# ITKS_685623_177_E3.net
KiCad netlist of a schematic drawn in Altium Designer
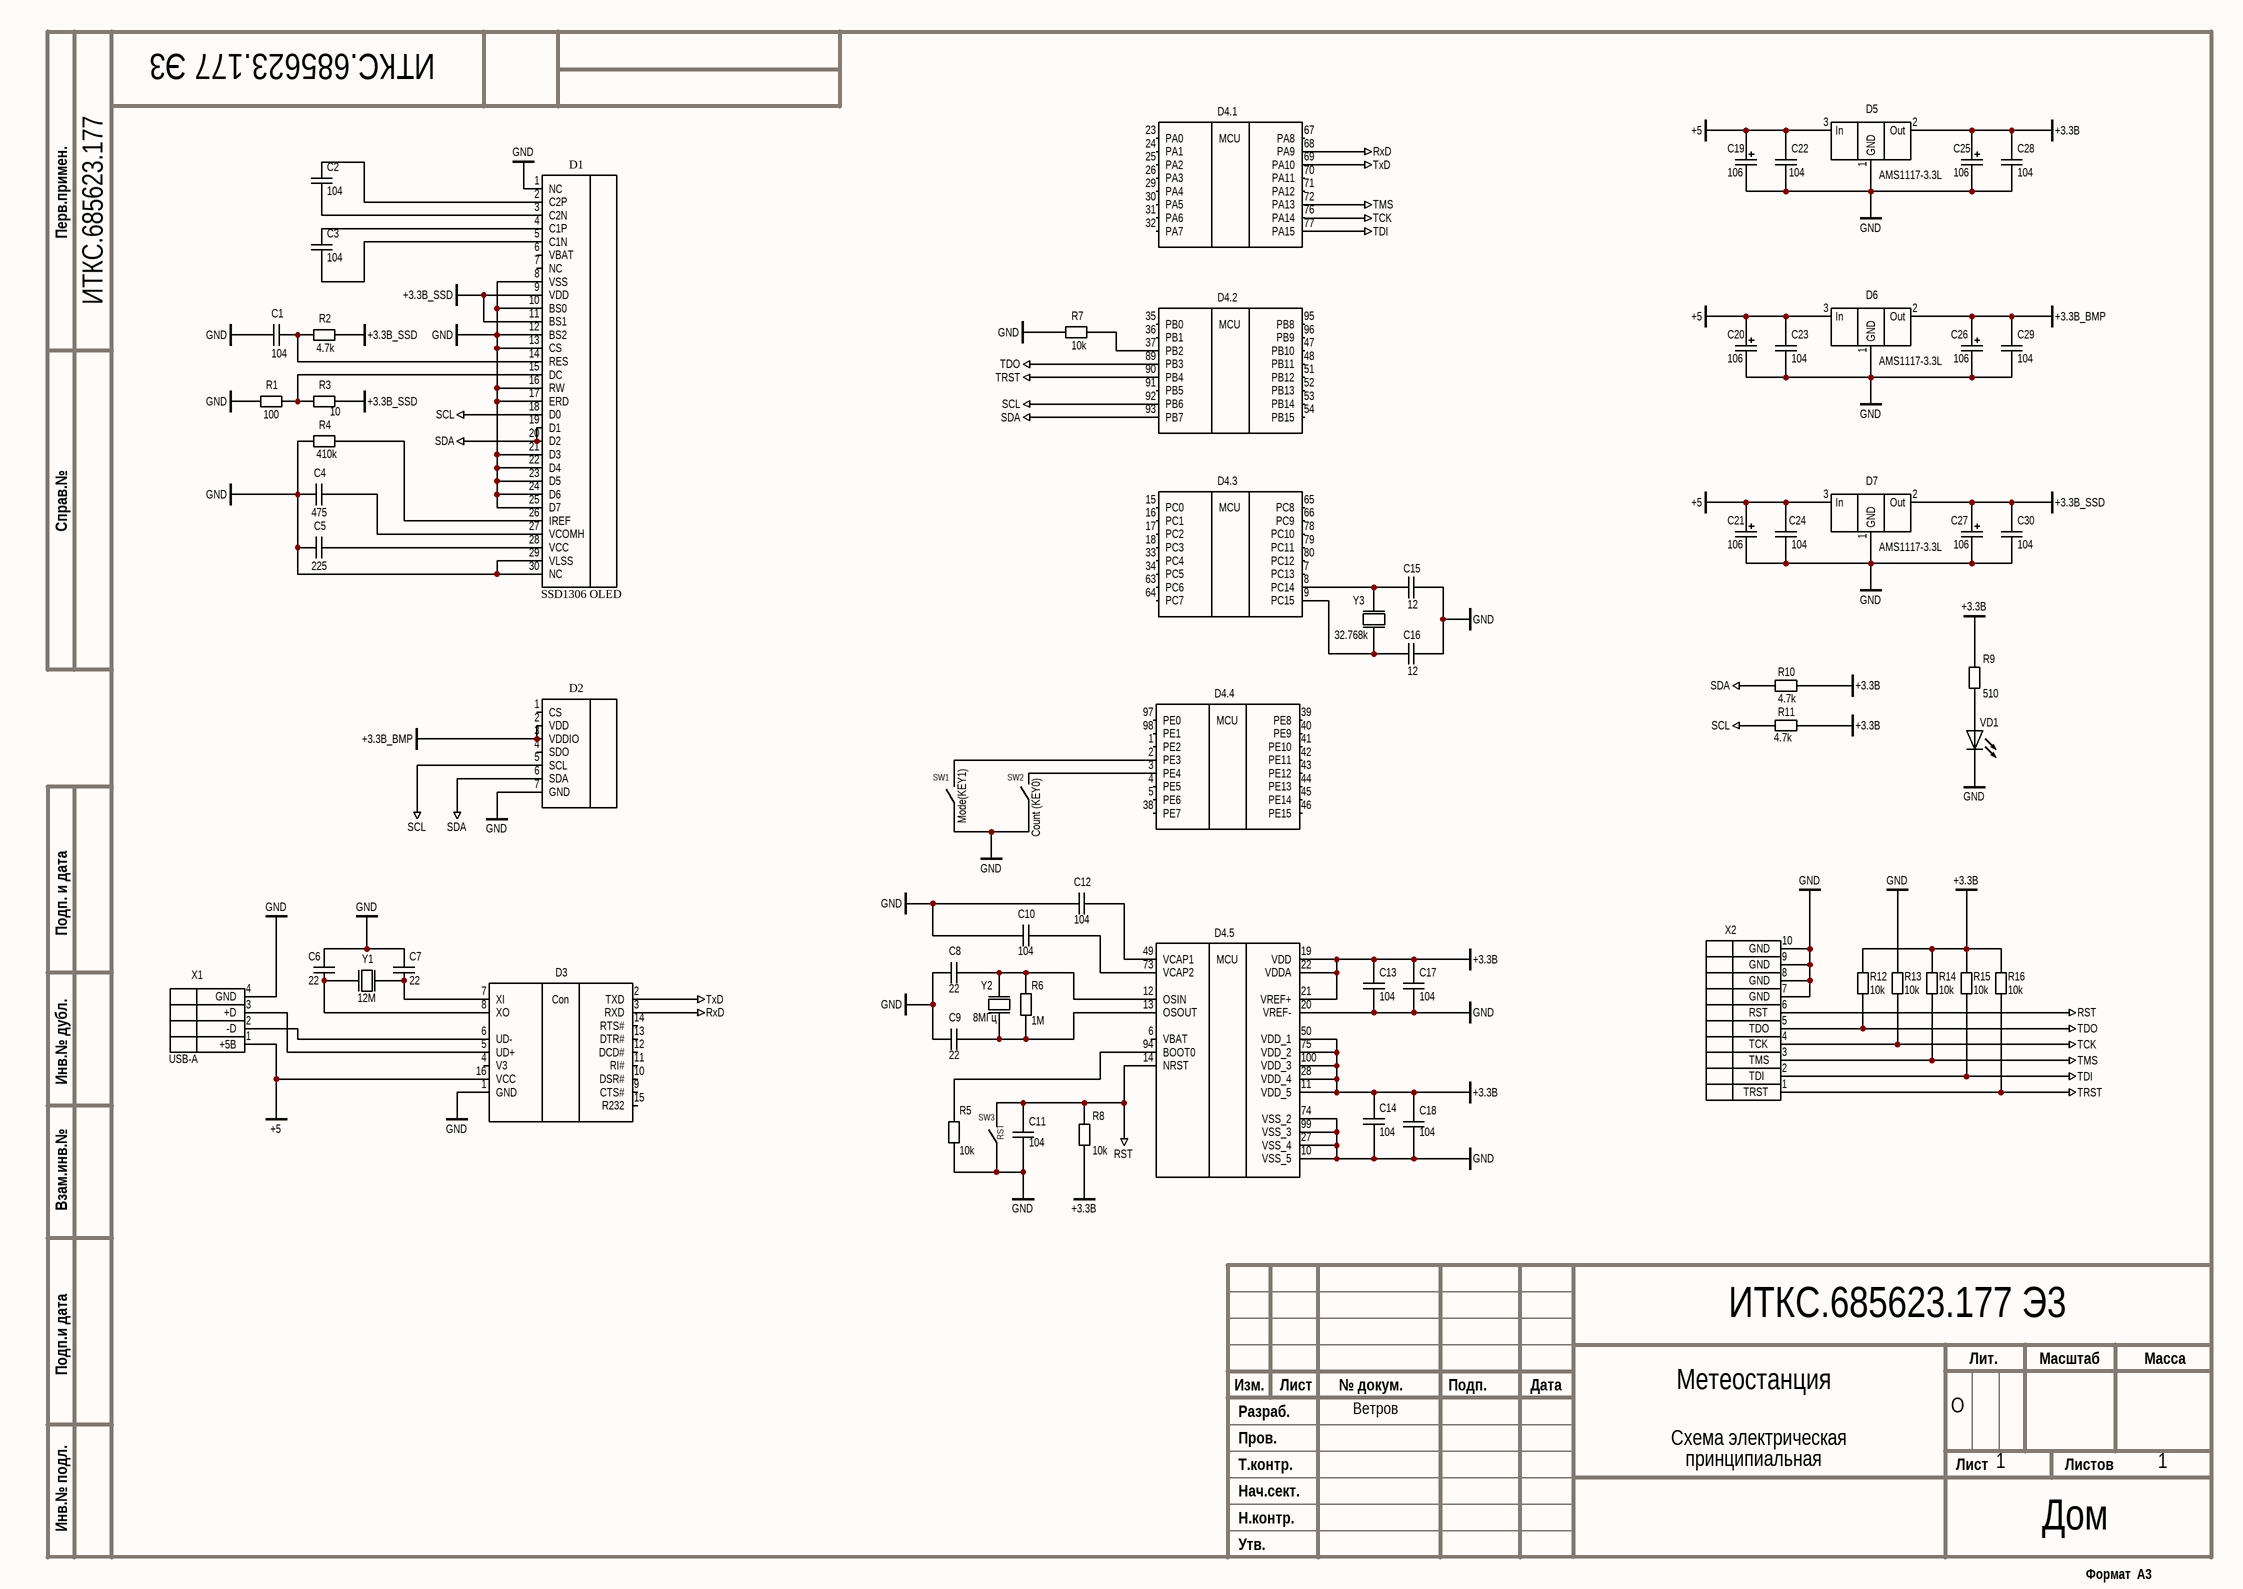
[diagram p0: ITKS.685623.177 E3.SchDoc]

(export (version "E")
  (design (tool "Eeschema 10.0.6"))
  (components
    (comp (ref "C1") (value "104") (footprint "0603") (libsource (lib "MainLib") (part "C")))
    (comp (ref "C2") (value "104") (footprint "0603") (libsource (lib "MainLib") (part "C")))
    (comp (ref "C3") (value "104") (footprint "0603") (libsource (lib "MainLib") (part "C")))
    (comp (ref "C4") (value "475") (footprint "0603") (libsource (lib "MainLib") (part "C")))
    (comp (ref "C5") (value "225") (footprint "0603") (libsource (lib "MainLib") (part "C")))
    (comp (ref "C6") (value "22") (footprint "0603") (libsource (lib "MainLib") (part "C")))
    (comp (ref "C7") (value "22") (footprint "0603") (libsource (lib "MainLib") (part "C")))
    (comp (ref "C8") (value "22") (footprint "0603") (libsource (lib "MainLib") (part "C")))
    (comp (ref "C9") (value "22") (footprint "0603") (libsource (lib "MainLib") (part "C")))
    (comp (ref "C10") (value "104") (footprint "0603") (libsource (lib "MainLib") (part "C")))
    (comp (ref "C11") (value "104") (footprint "0603") (libsource (lib "MainLib") (part "C")))
    (comp (ref "C12") (value "104") (footprint "0603") (libsource (lib "MainLib") (part "C")))
    (comp (ref "C13") (value "104") (footprint "0603") (libsource (lib "MainLib") (part "C")))
    (comp (ref "C14") (value "104") (footprint "0603") (libsource (lib "MainLib") (part "C")))
    (comp (ref "C15") (value "12") (footprint "0603") (libsource (lib "MainLib") (part "C")))
    (comp (ref "C16") (value "12") (footprint "0603") (libsource (lib "MainLib") (part "C")))
    (comp (ref "C17") (value "104") (footprint "0603") (libsource (lib "MainLib") (part "C")))
    (comp (ref "C18") (value "104") (footprint "0603") (libsource (lib "MainLib") (part "C")))
    (comp (ref "C19")
      (value "106")
      (footprint "EIA_6032–28")
      (description "TECAP EIA 6032–28")
      (libsource (lib "MainLib") (part "C+ TECAP"))
    )
    (comp (ref "C20")
      (value "106")
      (footprint "EIA_6032–28")
      (description "TECAP EIA 6032–28")
      (libsource (lib "MainLib") (part "C+ TECAP"))
    )
    (comp (ref "C21")
      (value "106")
      (footprint "EIA_6032–28")
      (description "TECAP EIA 6032–28")
      (libsource (lib "MainLib") (part "C+ TECAP"))
    )
    (comp (ref "C22") (value "104") (footprint "0603") (libsource (lib "MainLib") (part "C")))
    (comp (ref "C23") (value "104") (footprint "0603") (libsource (lib "MainLib") (part "C")))
    (comp (ref "C24") (value "104") (footprint "0603") (libsource (lib "MainLib") (part "C")))
    (comp (ref "C25")
      (value "106")
      (footprint "EIA_6032–28")
      (description "TECAP EIA 6032–28")
      (libsource (lib "MainLib") (part "C+ TECAP"))
    )
    (comp (ref "C26")
      (value "106")
      (footprint "EIA_6032–28")
      (description "TECAP EIA 6032–28")
      (libsource (lib "MainLib") (part "C+ TECAP"))
    )
    (comp (ref "C27")
      (value "106")
      (footprint "EIA_6032–28")
      (description "TECAP EIA 6032–28")
      (libsource (lib "MainLib") (part "C+ TECAP"))
    )
    (comp (ref "C28") (value "104") (footprint "0603") (libsource (lib "MainLib") (part "C")))
    (comp (ref "C29") (value "104") (footprint "0603") (libsource (lib "MainLib") (part "C")))
    (comp (ref "C30") (value "104") (footprint "0603") (libsource (lib "MainLib") (part "C")))
    (comp (ref "D1")
      (value "SSD1306 OLED")
      (footprint "SSD1306")
      (libsource (lib "MainLib") (part "SSD1306 OLED"))
    )
    (comp (ref "D2") (value "BMP180") (footprint "BMP180") (libsource (lib "MainLib") (part "BMP180")))
    (comp (ref "D3") (value "CH340G") (footprint "SOP16") (libsource (lib "MainLib") (part "CH340G")))
    (comp (ref "D4")
      (value "STM32F407VE")
      (footprint "LQFP100")
      (description "ARM3")
      (libsource (lib "MainLib") (part "STM32F407VE"))
    )
    (comp (ref "D5")
      (value "AMS1117-3.3L")
      (footprint "SOT223-4N")
      (libsource (lib "MainLib") (part "AMS1117-3.3L"))
    )
    (comp (ref "D6")
      (value "AMS1117-3.3L")
      (footprint "SOT223-4N")
      (libsource (lib "MainLib") (part "AMS1117-3.3L"))
    )
    (comp (ref "D7")
      (value "AMS1117-3.3L")
      (footprint "SOT223-4N")
      (libsource (lib "MainLib") (part "AMS1117-3.3L"))
    )
    (comp (ref "R1") (value "100") (footprint "0603") (libsource (lib "MainLib") (part "R")))
    (comp (ref "R2") (value "4.7k") (footprint "0603") (libsource (lib "MainLib") (part "R")))
    (comp (ref "R3") (value "10") (footprint "0603") (libsource (lib "MainLib") (part "R")))
    (comp (ref "R4") (value "410k") (footprint "0603") (libsource (lib "MainLib") (part "R")))
    (comp (ref "R5") (value "10k") (footprint "0603") (libsource (lib "MainLib") (part "R")))
    (comp (ref "R6") (value "1M") (footprint "0603") (libsource (lib "MainLib") (part "R")))
    (comp (ref "R7") (value "10k") (footprint "0603") (libsource (lib "MainLib") (part "R")))
    (comp (ref "R8") (value "10k") (footprint "0603") (libsource (lib "MainLib") (part "R")))
    (comp (ref "R9") (value "510") (footprint "0603") (libsource (lib "MainLib") (part "R")))
    (comp (ref "R10") (value "4.7k") (footprint "0603") (libsource (lib "MainLib") (part "R")))
    (comp (ref "R11") (value "4.7k") (footprint "0603") (libsource (lib "MainLib") (part "R")))
    (comp (ref "R12") (value "10k") (footprint "0603") (libsource (lib "MainLib") (part "R")))
    (comp (ref "R13") (value "10k") (footprint "0603") (libsource (lib "MainLib") (part "R")))
    (comp (ref "R14") (value "10k") (footprint "0603") (libsource (lib "MainLib") (part "R")))
    (comp (ref "R15") (value "10k") (footprint "0603") (libsource (lib "MainLib") (part "R")))
    (comp (ref "R16") (value "10k") (footprint "0603") (libsource (lib "MainLib") (part "R")))
    (comp (ref "SW1") (value "Mode(KEY1)") (footprint "0603") (libsource (lib "MainLib") (part "Button")))
    (comp (ref "SW2") (value "Count (KEY0)") (footprint "0603") (libsource (lib "MainLib") (part "Button")))
    (comp (ref "SW3") (value "RST") (footprint "0603") (libsource (lib "MainLib") (part "Button")))
    (comp (ref "VD1")
      (value "LED SMD 0805")
      (footprint "Led Diode 0805")
      (libsource (lib "MainLib") (part "LED SMD 0805"))
    )
    (comp (ref "X1")
      (value "USB-A")
      (footprint "USB-ASM (DS1098-B)")
      (libsource (lib "MainLib") (part "USB-A"))
    )
    (comp (ref "X2") (value "PLC-10") (footprint "PLC-10") (libsource (lib "MainLib") (part "PLC-10")))
    (comp (ref "Y1") (value "12M") (footprint "HC-49SM") (libsource (lib "MainLib") (part "BQ")))
    (comp (ref "Y2") (value "8МГц") (footprint "HC-49SM") (libsource (lib "MainLib") (part "BQ")))
    (comp (ref "Y3") (value "32.768k") (footprint "HC-49SM") (libsource (lib "MainLib") (part "BQ")))
  )
  (nets
    (net (code "1") (name "+3.3В") (class "Default")
      (node (ref "C13") (pin "1") (pinfunction "1_1") (pintype "passive"))
      (node (ref "C14") (pin "1") (pinfunction "1_1") (pintype "passive"))
      (node (ref "C17") (pin "1") (pinfunction "1_1") (pintype "passive"))
      (node (ref "C18") (pin "1") (pinfunction "1_1") (pintype "passive"))
      (node (ref "C25") (pin "1") (pinfunction "1_1") (pintype "passive"))
      (node (ref "C28") (pin "2") (pinfunction "2_2") (pintype "passive"))
      (node (ref "D4") (pin "100") (pinfunction "VDD_3_100") (pintype "passive"))
      (node (ref "D4") (pin "11") (pinfunction "VDD_5_11") (pintype "passive"))
      (node (ref "D4") (pin "19") (pinfunction "VDD_19") (pintype "passive"))
      (node (ref "D4") (pin "21") (pinfunction "VREF+_21") (pintype "passive"))
      (node (ref "D4") (pin "22") (pinfunction "VDDA_22") (pintype "passive"))
      (node (ref "D4") (pin "28") (pinfunction "VDD_4_28") (pintype "passive"))
      (node (ref "D4") (pin "50") (pinfunction "VDD_1_50") (pintype "passive"))
      (node (ref "D4") (pin "75") (pinfunction "VDD_2_75") (pintype "passive"))
      (node (ref "D5") (pin "2") (pinfunction "Out_2") (pintype "passive"))
      (node (ref "R10") (pin "2") (pinfunction "2_2") (pintype "passive"))
      (node (ref "R11") (pin "2") (pinfunction "2_2") (pintype "passive"))
      (node (ref "R12") (pin "2") (pinfunction "2_2") (pintype "passive"))
      (node (ref "R14") (pin "2") (pinfunction "2_2") (pintype "passive"))
      (node (ref "R15") (pin "2") (pinfunction "2_2") (pintype "passive"))
      (node (ref "R16") (pin "2") (pinfunction "2_2") (pintype "passive"))
      (node (ref "R8") (pin "2") (pinfunction "2_2") (pintype "passive"))
      (node (ref "R9") (pin "1") (pinfunction "1_1") (pintype "passive"))
    )
    (net (code "2") (name "+3.3В_BMP") (class "Default")
      (node (ref "C26") (pin "1") (pinfunction "1_1") (pintype "passive"))
      (node (ref "C29") (pin "2") (pinfunction "2_2") (pintype "passive"))
      (node (ref "D2") (pin "2") (pinfunction "VDD_2") (pintype "passive"))
      (node (ref "D2") (pin "3") (pinfunction "VDDIO_3") (pintype "passive"))
      (node (ref "D6") (pin "2") (pinfunction "Out_2") (pintype "passive"))
    )
    (net (code "3") (name "+3.3В_SSD") (class "Default")
      (node (ref "C27") (pin "1") (pinfunction "1_1") (pintype "passive"))
      (node (ref "C30") (pin "2") (pinfunction "2_2") (pintype "passive"))
      (node (ref "D1") (pin "11") (pinfunction "BS1_11") (pintype "passive"))
      (node (ref "D1") (pin "9") (pinfunction "VDD_9") (pintype "passive"))
      (node (ref "D7") (pin "2") (pinfunction "Out_2") (pintype "passive"))
      (node (ref "R2") (pin "1") (pinfunction "1_1") (pintype "passive"))
      (node (ref "R3") (pin "1") (pinfunction "1_1") (pintype "passive"))
    )
    (net (code "4") (name "+5") (class "Default")
      (node (ref "C19") (pin "1") (pinfunction "1_1") (pintype "passive"))
      (node (ref "C20") (pin "1") (pinfunction "1_1") (pintype "passive"))
      (node (ref "C21") (pin "1") (pinfunction "1_1") (pintype "passive"))
      (node (ref "C22") (pin "2") (pinfunction "2_2") (pintype "passive"))
      (node (ref "C23") (pin "2") (pinfunction "2_2") (pintype "passive"))
      (node (ref "C24") (pin "2") (pinfunction "2_2") (pintype "passive"))
      (node (ref "D3") (pin "16") (pinfunction "VCC_16") (pintype "passive"))
      (node (ref "D5") (pin "3") (pinfunction "In_3") (pintype "passive"))
      (node (ref "D6") (pin "3") (pinfunction "In_3") (pintype "passive"))
      (node (ref "D7") (pin "3") (pinfunction "In_3") (pintype "passive"))
      (node (ref "X1") (pin "1") (pinfunction "+5В_1") (pintype "passive"))
    )
    (net (code "5") (name "GND") (class "Default")
      (node (ref "C1") (pin "1") (pinfunction "1_1") (pintype "passive"))
      (node (ref "C10") (pin "2") (pinfunction "2_2") (pintype "passive"))
      (node (ref "C11") (pin "1") (pinfunction "1_1") (pintype "passive"))
      (node (ref "C12") (pin "2") (pinfunction "2_2") (pintype "passive"))
      (node (ref "C13") (pin "2") (pinfunction "2_2") (pintype "passive"))
      (node (ref "C14") (pin "2") (pinfunction "2_2") (pintype "passive"))
      (node (ref "C15") (pin "1") (pinfunction "1_1") (pintype "passive"))
      (node (ref "C16") (pin "1") (pinfunction "1_1") (pintype "passive"))
      (node (ref "C17") (pin "2") (pinfunction "2_2") (pintype "passive"))
      (node (ref "C18") (pin "2") (pinfunction "2_2") (pintype "passive"))
      (node (ref "C19") (pin "2") (pinfunction "2_2") (pintype "passive"))
      (node (ref "C20") (pin "2") (pinfunction "2_2") (pintype "passive"))
      (node (ref "C21") (pin "2") (pinfunction "2_2") (pintype "passive"))
      (node (ref "C22") (pin "1") (pinfunction "1_1") (pintype "passive"))
      (node (ref "C23") (pin "1") (pinfunction "1_1") (pintype "passive"))
      (node (ref "C24") (pin "1") (pinfunction "1_1") (pintype "passive"))
      (node (ref "C25") (pin "2") (pinfunction "2_2") (pintype "passive"))
      (node (ref "C26") (pin "2") (pinfunction "2_2") (pintype "passive"))
      (node (ref "C27") (pin "2") (pinfunction "2_2") (pintype "passive"))
      (node (ref "C28") (pin "1") (pinfunction "1_1") (pintype "passive"))
      (node (ref "C29") (pin "1") (pinfunction "1_1") (pintype "passive"))
      (node (ref "C30") (pin "1") (pinfunction "1_1") (pintype "passive"))
      (node (ref "C4") (pin "1") (pinfunction "1_1") (pintype "passive"))
      (node (ref "C5") (pin "1") (pinfunction "1_1") (pintype "passive"))
      (node (ref "C6") (pin "2") (pinfunction "2_2") (pintype "passive"))
      (node (ref "C7") (pin "2") (pinfunction "2_2") (pintype "passive"))
      (node (ref "C8") (pin "2") (pinfunction "2_2") (pintype "passive"))
      (node (ref "C9") (pin "2") (pinfunction "2_2") (pintype "passive"))
      (node (ref "D1") (pin "1") (pinfunction "NC_1") (pintype "passive"))
      (node (ref "D1") (pin "10") (pinfunction "BS0_10") (pintype "passive"))
      (node (ref "D1") (pin "12") (pinfunction "BS2_12") (pintype "passive"))
      (node (ref "D1") (pin "13") (pinfunction "CS_13") (pintype "passive"))
      (node (ref "D1") (pin "16") (pinfunction "RW_16") (pintype "passive"))
      (node (ref "D1") (pin "17") (pinfunction "ERD_17") (pintype "passive"))
      (node (ref "D1") (pin "21") (pinfunction "D3_21") (pintype "passive"))
      (node (ref "D1") (pin "22") (pinfunction "D4_22") (pintype "passive"))
      (node (ref "D1") (pin "23") (pinfunction "D5_23") (pintype "passive"))
      (node (ref "D1") (pin "24") (pinfunction "D6_24") (pintype "passive"))
      (node (ref "D1") (pin "25") (pinfunction "D7_25") (pintype "passive"))
      (node (ref "D1") (pin "29") (pinfunction "VLSS_29") (pintype "passive"))
      (node (ref "D1") (pin "30") (pinfunction "NC_30") (pintype "passive"))
      (node (ref "D1") (pin "8") (pinfunction "VSS_8") (pintype "passive"))
      (node (ref "D2") (pin "7") (pinfunction "GND_7") (pintype "passive"))
      (node (ref "D3") (pin "1") (pinfunction "GND_1") (pintype "passive"))
      (node (ref "D4") (pin "10") (pinfunction "VSS_5_10") (pintype "passive"))
      (node (ref "D4") (pin "20") (pinfunction "VREF-_20") (pintype "passive"))
      (node (ref "D4") (pin "27") (pinfunction "VSS_4_27") (pintype "passive"))
      (node (ref "D4") (pin "74") (pinfunction "VSS_2_74") (pintype "passive"))
      (node (ref "D4") (pin "99") (pinfunction "VSS_3_99") (pintype "passive"))
      (node (ref "D5") (pin "1") (pinfunction "GND_1") (pintype "passive"))
      (node (ref "D6") (pin "1") (pinfunction "GND_1") (pintype "passive"))
      (node (ref "D7") (pin "1") (pinfunction "GND_1") (pintype "passive"))
      (node (ref "R1") (pin "2") (pinfunction "2_2") (pintype "passive"))
      (node (ref "R13") (pin "2") (pinfunction "2_2") (pintype "passive"))
      (node (ref "R4") (pin "2") (pinfunction "2_2") (pintype "passive"))
      (node (ref "R5") (pin "2") (pinfunction "2_2") (pintype "passive"))
      (node (ref "R7") (pin "1") (pinfunction "1_1") (pintype "passive"))
      (node (ref "SW1") (pin "1") (pinfunction "1_1") (pintype "passive"))
      (node (ref "SW2") (pin "1") (pinfunction "1_1") (pintype "passive"))
      (node (ref "SW3") (pin "1") (pinfunction "1_1") (pintype "passive"))
      (node (ref "VD1") (pin "K") (pinfunction "K_K") (pintype "passive"))
      (node (ref "X1") (pin "4") (pinfunction "GND_4") (pintype "passive"))
      (node (ref "X2") (pin "10") (pintype "passive"))
      (node (ref "X2") (pin "7") (pintype "passive"))
      (node (ref "X2") (pin "8") (pintype "passive"))
      (node (ref "X2") (pin "9") (pintype "passive"))
    )
    (net (code "6") (name "Net-(D1-C1N)") (class "Default")
      (node (ref "C3") (pin "2") (pinfunction "2_2") (pintype "passive"))
      (node (ref "D1") (pin "5") (pinfunction "C1N_5") (pintype "passive"))
    )
    (net (code "7") (name "Net-(D1-C1P)") (class "Default")
      (node (ref "C3") (pin "1") (pinfunction "1_1") (pintype "passive"))
      (node (ref "D1") (pin "4") (pinfunction "C1P_4") (pintype "passive"))
    )
    (net (code "8") (name "Net-(D1-C2N)") (class "Default")
      (node (ref "C2") (pin "2") (pinfunction "2_2") (pintype "passive"))
      (node (ref "D1") (pin "3") (pinfunction "C2N_3") (pintype "passive"))
    )
    (net (code "9") (name "Net-(D1-C2P)") (class "Default")
      (node (ref "C2") (pin "1") (pinfunction "1_1") (pintype "passive"))
      (node (ref "D1") (pin "2") (pinfunction "C2P_2") (pintype "passive"))
    )
    (net (code "10") (name "Net-(D1-DC)") (class "Default")
      (node (ref "D1") (pin "15") (pinfunction "DC_15") (pintype "passive"))
      (node (ref "R1") (pin "1") (pinfunction "1_1") (pintype "passive"))
      (node (ref "R3") (pin "2") (pinfunction "2_2") (pintype "passive"))
    )
    (net (code "11") (name "Net-(D1-IREF)") (class "Default")
      (node (ref "D1") (pin "26") (pinfunction "IREF_26") (pintype "passive"))
      (node (ref "R4") (pin "1") (pinfunction "1_1") (pintype "passive"))
    )
    (net (code "12") (name "Net-(D1-RES)") (class "Default")
      (node (ref "C1") (pin "2") (pinfunction "2_2") (pintype "passive"))
      (node (ref "D1") (pin "14") (pinfunction "RES_14") (pintype "passive"))
      (node (ref "R2") (pin "2") (pinfunction "2_2") (pintype "passive"))
    )
    (net (code "13") (name "Net-(D1-VCC)") (class "Default")
      (node (ref "C5") (pin "2") (pinfunction "2_2") (pintype "passive"))
      (node (ref "D1") (pin "28") (pinfunction "VCC_28") (pintype "passive"))
    )
    (net (code "14") (name "Net-(D1-VCOMH)") (class "Default")
      (node (ref "C4") (pin "2") (pinfunction "2_2") (pintype "passive"))
      (node (ref "D1") (pin "27") (pinfunction "VCOMH_27") (pintype "passive"))
    )
    (net (code "15") (name "Net-(D3-UD+)") (class "Default")
      (node (ref "D3") (pin "5") (pinfunction "UD+_5") (pintype "passive"))
      (node (ref "X1") (pin "3") (pinfunction "+D_3") (pintype "passive"))
    )
    (net (code "16") (name "Net-(D3-UD-)") (class "Default")
      (node (ref "D3") (pin "6") (pinfunction "UD-_6") (pintype "passive"))
      (node (ref "X1") (pin "2") (pinfunction "-D_2") (pintype "passive"))
    )
    (net (code "17") (name "Net-(D3-XI)") (class "Default")
      (node (ref "C7") (pin "1") (pinfunction "1_1") (pintype "passive"))
      (node (ref "D3") (pin "7") (pinfunction "XI_7") (pintype "passive"))
      (node (ref "Y1") (pin "1") (pinfunction "1_1") (pintype "passive"))
    )
    (net (code "18") (name "Net-(D3-XO)") (class "Default")
      (node (ref "C6") (pin "1") (pinfunction "1_1") (pintype "passive"))
      (node (ref "D3") (pin "8") (pinfunction "XO_8") (pintype "passive"))
      (node (ref "Y1") (pin "2") (pinfunction "2_2") (pintype "passive"))
    )
    (net (code "19") (name "Net-(D4B-PB2)") (class "Default")
      (node (ref "D4") (pin "37") (pinfunction "PB2_37") (pintype "passive"))
      (node (ref "R7") (pin "2") (pinfunction "2_2") (pintype "passive"))
    )
    (net (code "20") (name "Net-(D4C-PC14)") (class "Default")
      (node (ref "C15") (pin "2") (pinfunction "2_2") (pintype "passive"))
      (node (ref "D4") (pin "8") (pinfunction "PC14_8") (pintype "passive"))
      (node (ref "Y3") (pin "2") (pinfunction "2_2") (pintype "passive"))
    )
    (net (code "21") (name "Net-(D4C-PC15)") (class "Default")
      (node (ref "C16") (pin "2") (pinfunction "2_2") (pintype "passive"))
      (node (ref "D4") (pin "9") (pinfunction "PC15_9") (pintype "passive"))
      (node (ref "Y3") (pin "1") (pinfunction "1_1") (pintype "passive"))
    )
    (net (code "22") (name "Net-(D4E-PE3)") (class "Default")
      (node (ref "D4") (pin "2") (pinfunction "PE3_2") (pintype "passive"))
      (node (ref "SW1") (pin "2") (pinfunction "2_2") (pintype "passive"))
    )
    (net (code "23") (name "Net-(D4E-PE4)") (class "Default")
      (node (ref "D4") (pin "3") (pinfunction "PE4_3") (pintype "passive"))
      (node (ref "SW2") (pin "2") (pinfunction "2_2") (pintype "passive"))
    )
    (net (code "24") (name "Net-(D4F-BOOT0)") (class "Default")
      (node (ref "D4") (pin "94") (pinfunction "BOOT0_94") (pintype "passive"))
      (node (ref "R5") (pin "1") (pinfunction "1_1") (pintype "passive"))
    )
    (net (code "25") (name "Net-(D4F-OSIN)") (class "Default")
      (node (ref "C8") (pin "1") (pinfunction "1_1") (pintype "passive"))
      (node (ref "D4") (pin "12") (pinfunction "OSIN_12") (pintype "passive"))
      (node (ref "R6") (pin "2") (pinfunction "2_2") (pintype "passive"))
      (node (ref "Y2") (pin "2") (pinfunction "2_2") (pintype "passive"))
    )
    (net (code "26") (name "Net-(D4F-OSOUT)") (class "Default")
      (node (ref "C9") (pin "1") (pinfunction "1_1") (pintype "passive"))
      (node (ref "D4") (pin "13") (pinfunction "OSOUT_13") (pintype "passive"))
      (node (ref "R6") (pin "1") (pinfunction "1_1") (pintype "passive"))
      (node (ref "Y2") (pin "1") (pinfunction "1_1") (pintype "passive"))
    )
    (net (code "27") (name "Net-(D4F-VCAP1)") (class "Default")
      (node (ref "C12") (pin "1") (pinfunction "1_1") (pintype "passive"))
      (node (ref "D4") (pin "49") (pinfunction "VCAP1_49") (pintype "passive"))
    )
    (net (code "28") (name "Net-(D4F-VCAP2)") (class "Default")
      (node (ref "C10") (pin "1") (pinfunction "1_1") (pintype "passive"))
      (node (ref "D4") (pin "73") (pinfunction "VCAP2_73") (pintype "passive"))
    )
    (net (code "29") (name "Net-(R9-Pad2)") (class "Default")
      (node (ref "R9") (pin "2") (pinfunction "2_2") (pintype "passive"))
      (node (ref "VD1") (pin "A") (pinfunction "A_A") (pintype "passive"))
    )
    (net (code "30") (name "RST") (class "Default")
      (node (ref "C11") (pin "2") (pinfunction "2_2") (pintype "passive"))
      (node (ref "D4") (pin "14") (pinfunction "NRST_14") (pintype "passive"))
      (node (ref "R8") (pin "1") (pinfunction "1_1") (pintype "passive"))
      (node (ref "SW3") (pin "2") (pinfunction "2_2") (pintype "passive"))
      (node (ref "X2") (pin "6") (pintype "passive"))
    )
    (net (code "31") (name "RxD") (class "Default")
      (node (ref "D3") (pin "3") (pinfunction "RXD_3") (pintype "passive"))
      (node (ref "D4") (pin "68") (pinfunction "PA9_68") (pintype "passive"))
    )
    (net (code "32") (name "SCL") (class "Default")
      (node (ref "D1") (pin "18") (pinfunction "D0_18") (pintype "passive"))
      (node (ref "D2") (pin "5") (pinfunction "SCL_5") (pintype "passive"))
      (node (ref "D4") (pin "92") (pinfunction "PB6_92") (pintype "passive"))
      (node (ref "R11") (pin "1") (pinfunction "1_1") (pintype "passive"))
    )
    (net (code "33") (name "SDA") (class "Default")
      (node (ref "D1") (pin "19") (pinfunction "D1_19") (pintype "passive"))
      (node (ref "D1") (pin "20") (pinfunction "D2_20") (pintype "passive"))
      (node (ref "D2") (pin "6") (pinfunction "SDA_6") (pintype "passive"))
      (node (ref "D4") (pin "93") (pinfunction "PB7_93") (pintype "passive"))
      (node (ref "R10") (pin "1") (pinfunction "1_1") (pintype "passive"))
    )
    (net (code "34") (name "TCK") (class "Default")
      (node (ref "D4") (pin "76") (pinfunction "PA14_76") (pintype "passive"))
      (node (ref "R13") (pin "1") (pinfunction "1_1") (pintype "passive"))
      (node (ref "X2") (pin "4") (pintype "passive"))
    )
    (net (code "35") (name "TDI") (class "Default")
      (node (ref "D4") (pin "77") (pinfunction "PA15_77") (pintype "passive"))
      (node (ref "R15") (pin "1") (pinfunction "1_1") (pintype "passive"))
      (node (ref "X2") (pin "2") (pintype "passive"))
    )
    (net (code "36") (name "TDO") (class "Default")
      (node (ref "D4") (pin "89") (pinfunction "PB3_89") (pintype "passive"))
      (node (ref "R12") (pin "1") (pinfunction "1_1") (pintype "passive"))
      (node (ref "X2") (pin "5") (pintype "passive"))
    )
    (net (code "37") (name "TMS") (class "Default")
      (node (ref "D4") (pin "72") (pinfunction "PA13_72") (pintype "passive"))
      (node (ref "R14") (pin "1") (pinfunction "1_1") (pintype "passive"))
      (node (ref "X2") (pin "3") (pintype "passive"))
    )
    (net (code "38") (name "TRST") (class "Default")
      (node (ref "D4") (pin "90") (pinfunction "PB4_90") (pintype "passive"))
      (node (ref "R16") (pin "1") (pinfunction "1_1") (pintype "passive"))
      (node (ref "X2") (pin "1") (pintype "passive"))
    )
    (net (code "39") (name "TxD") (class "Default")
      (node (ref "D3") (pin "2") (pinfunction "TXD_2") (pintype "passive"))
      (node (ref "D4") (pin "69") (pinfunction "PA10_69") (pintype "passive"))
    )
    (net (code "40") (name "unconnected-(D1-NC-Pad7)") (class "Default")
      (node (ref "D1") (pin "7") (pinfunction "NC_7") (pintype "passive"))
    )
    (net (code "41") (name "unconnected-(D1-VBAT-Pad6)") (class "Default")
      (node (ref "D1") (pin "6") (pinfunction "VBAT_6") (pintype "passive"))
    )
    (net (code "42") (name "unconnected-(D2-CS-Pad1)") (class "Default")
      (node (ref "D2") (pin "1") (pinfunction "CS_1") (pintype "passive"))
    )
    (net (code "43") (name "unconnected-(D2-SDO-Pad4)") (class "Default")
      (node (ref "D2") (pin "4") (pinfunction "SDO_4") (pintype "passive"))
    )
    (net (code "44") (name "unconnected-(D3-CTS#-Pad9)") (class "Default")
      (node (ref "D3") (pin "9") (pinfunction "CTS#_9") (pintype "passive"))
    )
    (net (code "45") (name "unconnected-(D3-DCD#-Pad12)") (class "Default")
      (node (ref "D3") (pin "12") (pinfunction "DCD#_12") (pintype "passive"))
    )
    (net (code "46") (name "unconnected-(D3-DSR#-Pad10)") (class "Default")
      (node (ref "D3") (pin "10") (pinfunction "DSR#_10") (pintype "passive"))
    )
    (net (code "47") (name "unconnected-(D3-DTR#-Pad13)") (class "Default")
      (node (ref "D3") (pin "13") (pinfunction "DTR#_13") (pintype "passive"))
    )
    (net (code "48") (name "unconnected-(D3-R232-Pad15)") (class "Default")
      (node (ref "D3") (pin "15") (pinfunction "R232_15") (pintype "passive"))
    )
    (net (code "49") (name "unconnected-(D3-RI#-Pad11)") (class "Default")
      (node (ref "D3") (pin "11") (pinfunction "RI#_11") (pintype "passive"))
    )
    (net (code "50") (name "unconnected-(D3-RTS#-Pad14)") (class "Default")
      (node (ref "D3") (pin "14") (pinfunction "RTS#_14") (pintype "passive"))
    )
    (net (code "51") (name "unconnected-(D3-V3-Pad4)") (class "Default")
      (node (ref "D3") (pin "4") (pinfunction "V3_4") (pintype "passive"))
    )
    (net (code "52") (name "unconnected-(D4A-PA0-Pad23)") (class "Default")
      (node (ref "D4") (pin "23") (pinfunction "PA0_23") (pintype "passive"))
    )
    (net (code "53") (name "unconnected-(D4A-PA1-Pad24)") (class "Default")
      (node (ref "D4") (pin "24") (pinfunction "PA1_24") (pintype "passive"))
    )
    (net (code "54") (name "unconnected-(D4A-PA2-Pad25)") (class "Default")
      (node (ref "D4") (pin "25") (pinfunction "PA2_25") (pintype "passive"))
    )
    (net (code "55") (name "unconnected-(D4A-PA3-Pad26)") (class "Default")
      (node (ref "D4") (pin "26") (pinfunction "PA3_26") (pintype "passive"))
    )
    (net (code "56") (name "unconnected-(D4A-PA4-Pad29)") (class "Default")
      (node (ref "D4") (pin "29") (pinfunction "PA4_29") (pintype "passive"))
    )
    (net (code "57") (name "unconnected-(D4A-PA5-Pad30)") (class "Default")
      (node (ref "D4") (pin "30") (pinfunction "PA5_30") (pintype "passive"))
    )
    (net (code "58") (name "unconnected-(D4A-PA6-Pad31)") (class "Default")
      (node (ref "D4") (pin "31") (pinfunction "PA6_31") (pintype "passive"))
    )
    (net (code "59") (name "unconnected-(D4A-PA7-Pad32)") (class "Default")
      (node (ref "D4") (pin "32") (pinfunction "PA7_32") (pintype "passive"))
    )
    (net (code "60") (name "unconnected-(D4A-PA8-Pad67)") (class "Default")
      (node (ref "D4") (pin "67") (pinfunction "PA8_67") (pintype "passive"))
    )
    (net (code "61") (name "unconnected-(D4A-PA11-Pad70)") (class "Default")
      (node (ref "D4") (pin "70") (pinfunction "PA11_70") (pintype "passive"))
    )
    (net (code "62") (name "unconnected-(D4A-PA12-Pad71)") (class "Default")
      (node (ref "D4") (pin "71") (pinfunction "PA12_71") (pintype "passive"))
    )
    (net (code "63") (name "unconnected-(D4B-PB0-Pad35)") (class "Default")
      (node (ref "D4") (pin "35") (pinfunction "PB0_35") (pintype "passive"))
    )
    (net (code "64") (name "unconnected-(D4B-PB1-Pad36)") (class "Default")
      (node (ref "D4") (pin "36") (pinfunction "PB1_36") (pintype "passive"))
    )
    (net (code "65") (name "unconnected-(D4B-PB5-Pad91)") (class "Default")
      (node (ref "D4") (pin "91") (pinfunction "PB5_91") (pintype "passive"))
    )
    (net (code "66") (name "unconnected-(D4B-PB8-Pad95)") (class "Default")
      (node (ref "D4") (pin "95") (pinfunction "PB8_95") (pintype "passive"))
    )
    (net (code "67") (name "unconnected-(D4B-PB9-Pad96)") (class "Default")
      (node (ref "D4") (pin "96") (pinfunction "PB9_96") (pintype "passive"))
    )
    (net (code "68") (name "unconnected-(D4B-PB10-Pad47)") (class "Default")
      (node (ref "D4") (pin "47") (pinfunction "PB10_47") (pintype "passive"))
    )
    (net (code "69") (name "unconnected-(D4B-PB11-Pad48)") (class "Default")
      (node (ref "D4") (pin "48") (pinfunction "PB11_48") (pintype "passive"))
    )
    (net (code "70") (name "unconnected-(D4B-PB12-Pad51)") (class "Default")
      (node (ref "D4") (pin "51") (pinfunction "PB12_51") (pintype "passive"))
    )
    (net (code "71") (name "unconnected-(D4B-PB13-Pad52)") (class "Default")
      (node (ref "D4") (pin "52") (pinfunction "PB13_52") (pintype "passive"))
    )
    (net (code "72") (name "unconnected-(D4B-PB14-Pad53)") (class "Default")
      (node (ref "D4") (pin "53") (pinfunction "PB14_53") (pintype "passive"))
    )
    (net (code "73") (name "unconnected-(D4B-PB15-Pad54)") (class "Default")
      (node (ref "D4") (pin "54") (pinfunction "PB15_54") (pintype "passive"))
    )
    (net (code "74") (name "unconnected-(D4C-PC0-Pad15)") (class "Default")
      (node (ref "D4") (pin "15") (pinfunction "PC0_15") (pintype "passive"))
    )
    (net (code "75") (name "unconnected-(D4C-PC1-Pad16)") (class "Default")
      (node (ref "D4") (pin "16") (pinfunction "PC1_16") (pintype "passive"))
    )
    (net (code "76") (name "unconnected-(D4C-PC2-Pad17)") (class "Default")
      (node (ref "D4") (pin "17") (pinfunction "PC2_17") (pintype "passive"))
    )
    (net (code "77") (name "unconnected-(D4C-PC3-Pad18)") (class "Default")
      (node (ref "D4") (pin "18") (pinfunction "PC3_18") (pintype "passive"))
    )
    (net (code "78") (name "unconnected-(D4C-PC4-Pad33)") (class "Default")
      (node (ref "D4") (pin "33") (pinfunction "PC4_33") (pintype "passive"))
    )
    (net (code "79") (name "unconnected-(D4C-PC5-Pad34)") (class "Default")
      (node (ref "D4") (pin "34") (pinfunction "PC5_34") (pintype "passive"))
    )
    (net (code "80") (name "unconnected-(D4C-PC6-Pad63)") (class "Default")
      (node (ref "D4") (pin "63") (pinfunction "PC6_63") (pintype "passive"))
    )
    (net (code "81") (name "unconnected-(D4C-PC7-Pad64)") (class "Default")
      (node (ref "D4") (pin "64") (pinfunction "PC7_64") (pintype "passive"))
    )
    (net (code "82") (name "unconnected-(D4C-PC8-Pad65)") (class "Default")
      (node (ref "D4") (pin "65") (pinfunction "PC8_65") (pintype "passive"))
    )
    (net (code "83") (name "unconnected-(D4C-PC9-Pad66)") (class "Default")
      (node (ref "D4") (pin "66") (pinfunction "PC9_66") (pintype "passive"))
    )
    (net (code "84") (name "unconnected-(D4C-PC10-Pad78)") (class "Default")
      (node (ref "D4") (pin "78") (pinfunction "PC10_78") (pintype "passive"))
    )
    (net (code "85") (name "unconnected-(D4C-PC11-Pad79)") (class "Default")
      (node (ref "D4") (pin "79") (pinfunction "PC11_79") (pintype "passive"))
    )
    (net (code "86") (name "unconnected-(D4C-PC12-Pad80)") (class "Default")
      (node (ref "D4") (pin "80") (pinfunction "PC12_80") (pintype "passive"))
    )
    (net (code "87") (name "unconnected-(D4C-PC13-Pad7)") (class "Default")
      (node (ref "D4") (pin "7") (pinfunction "PC13_7") (pintype "passive"))
    )
    (net (code "88") (name "unconnected-(D4E-PE0-Pad97)") (class "Default")
      (node (ref "D4") (pin "97") (pinfunction "PE0_97") (pintype "passive"))
    )
    (net (code "89") (name "unconnected-(D4E-PE1-Pad98)") (class "Default")
      (node (ref "D4") (pin "98") (pinfunction "PE1_98") (pintype "passive"))
    )
    (net (code "90") (name "unconnected-(D4E-PE2-Pad1)") (class "Default")
      (node (ref "D4") (pin "1") (pinfunction "PE2_1") (pintype "passive"))
    )
    (net (code "91") (name "unconnected-(D4E-PE5-Pad4)") (class "Default")
      (node (ref "D4") (pin "4") (pinfunction "PE5_4") (pintype "passive"))
    )
    (net (code "92") (name "unconnected-(D4E-PE6-Pad5)") (class "Default")
      (node (ref "D4") (pin "5") (pinfunction "PE6_5") (pintype "passive"))
    )
    (net (code "93") (name "unconnected-(D4E-PE7-Pad38)") (class "Default")
      (node (ref "D4") (pin "38") (pinfunction "PE7_38") (pintype "passive"))
    )
    (net (code "94") (name "unconnected-(D4E-PE8-Pad39)") (class "Default")
      (node (ref "D4") (pin "39") (pinfunction "PE8_39") (pintype "passive"))
    )
    (net (code "95") (name "unconnected-(D4E-PE9-Pad40)") (class "Default")
      (node (ref "D4") (pin "40") (pinfunction "PE9_40") (pintype "passive"))
    )
    (net (code "96") (name "unconnected-(D4E-PE10-Pad41)") (class "Default")
      (node (ref "D4") (pin "41") (pinfunction "PE10_41") (pintype "passive"))
    )
    (net (code "97") (name "unconnected-(D4E-PE11-Pad42)") (class "Default")
      (node (ref "D4") (pin "42") (pinfunction "PE11_42") (pintype "passive"))
    )
    (net (code "98") (name "unconnected-(D4E-PE12-Pad43)") (class "Default")
      (node (ref "D4") (pin "43") (pinfunction "PE12_43") (pintype "passive"))
    )
    (net (code "99") (name "unconnected-(D4E-PE13-Pad44)") (class "Default")
      (node (ref "D4") (pin "44") (pinfunction "PE13_44") (pintype "passive"))
    )
    (net (code "100") (name "unconnected-(D4E-PE14-Pad45)") (class "Default")
      (node (ref "D4") (pin "45") (pinfunction "PE14_45") (pintype "passive"))
    )
    (net (code "101") (name "unconnected-(D4E-PE15-Pad46)") (class "Default")
      (node (ref "D4") (pin "46") (pinfunction "PE15_46") (pintype "passive"))
    )
    (net (code "102") (name "unconnected-(D4F-VBAT-Pad6)") (class "Default")
      (node (ref "D4") (pin "6") (pinfunction "VBAT_6") (pintype "passive"))
    )
  )
)
